# AH3761.net
KiCad netlist of a schematic drawn in EAGLE
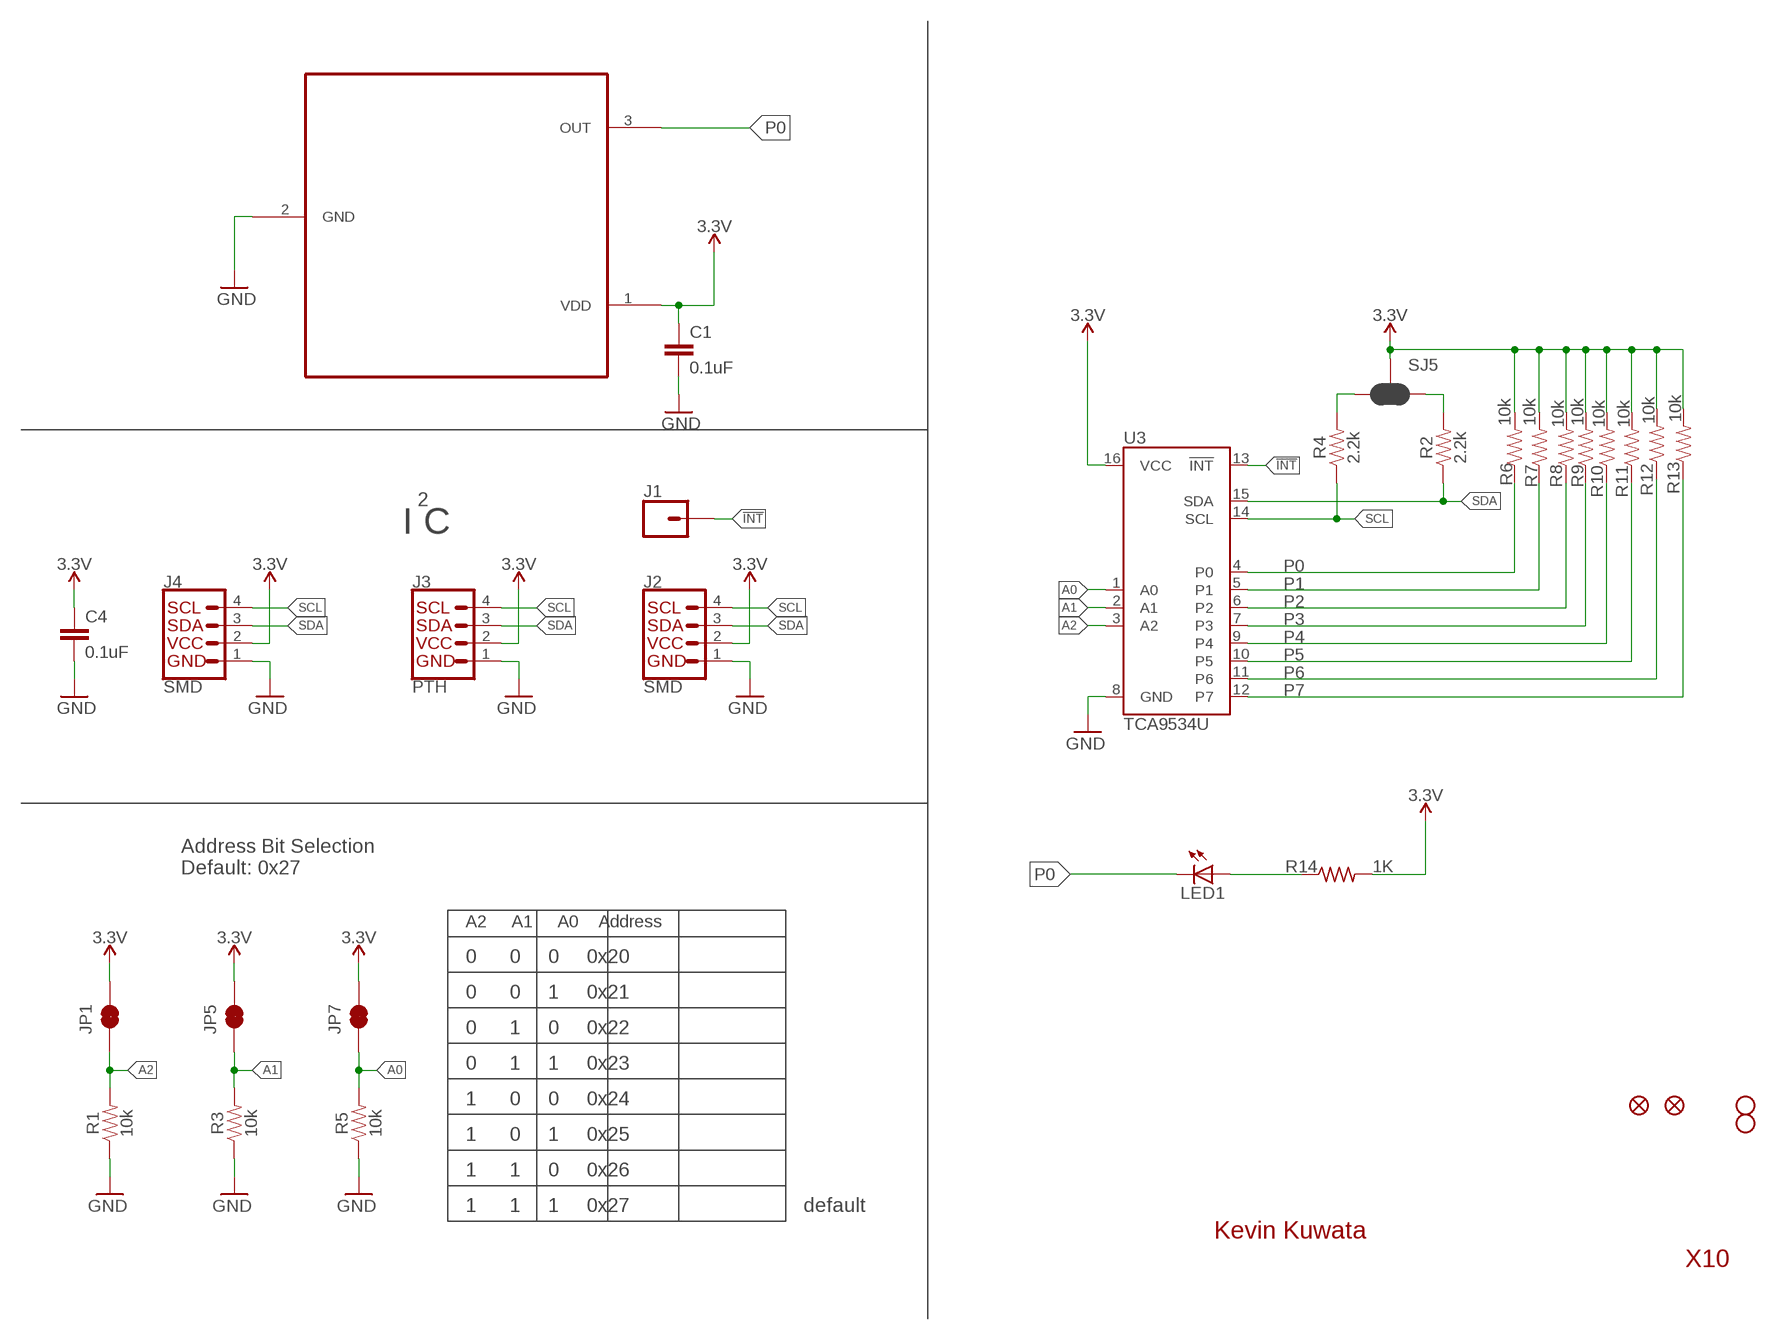
[diagram p0: schematic, sheet 1]

(export (version "E")
  (design (tool "Eeschema 10.0.6"))
  (components
    (comp (ref "C1")
      (value "0.1uF")
      (footprint "eagle-import:0603")
      (libsource (lib "eagle-import") (part "0.1UF-0603-25V-(+80/-20%)"))
    )
    (comp (ref "C4")
      (value "0.1uF")
      (footprint "eagle-import:0603")
      (libsource (lib "eagle-import") (part "0.1UF-0603-25V-(+80/-20%)"))
    )
    (comp (ref "J1")
      (value "CONN_01PTH_NO_SILK_YES_STOP")
      (footprint "eagle-import:1X01_NO_SILK")
      (libsource (lib "eagle-import") (part "CONN_01PTH_NO_SILK_YES_STOP"))
    )
    (comp (ref "J2")
      (value "SMD")
      (footprint "eagle-import:1X04_1MM_RA")
      (libsource (lib "eagle-import") (part "I2C_STANDARDJS-1MM"))
    )
    (comp (ref "J3")
      (value "PTH")
      (footprint "eagle-import:1X04_NO_SILK")
      (libsource (lib "eagle-import") (part "I2C_STANDARD_NO_SILK"))
    )
    (comp (ref "J4")
      (value "SMD")
      (footprint "eagle-import:1X04_1MM_RA")
      (libsource (lib "eagle-import") (part "I2C_STANDARDJS-1MM"))
    )
    (comp (ref "JP1")
      (value "JUMPER-SMT_2_NC_TRACE_NO-SILK")
      (footprint "eagle-import:SMT-JUMPER_2_NC_TRACE_NO-SILK")
      (libsource (lib "eagle-import") (part "JUMPER-SMT_2_NC_TRACE_NO-SILK"))
    )
    (comp (ref "JP2")
      (value "FIDUCIALUFIDUCIAL")
      (footprint "eagle-import:MICRO-FIDUCIAL")
      (libsource (lib "eagle-import") (part "FIDUCIALUFIDUCIAL"))
    )
    (comp (ref "JP3")
      (value "STAND-OFF")
      (footprint "eagle-import:STAND-OFF")
      (libsource (lib "eagle-import") (part "STAND-OFF"))
    )
    (comp (ref "JP4")
      (value "STAND-OFF")
      (footprint "eagle-import:STAND-OFF")
      (libsource (lib "eagle-import") (part "STAND-OFF"))
    )
    (comp (ref "JP5")
      (value "JUMPER-SMT_2_NC_TRACE_NO-SILK")
      (footprint "eagle-import:SMT-JUMPER_2_NC_TRACE_NO-SILK")
      (libsource (lib "eagle-import") (part "JUMPER-SMT_2_NC_TRACE_NO-SILK"))
    )
    (comp (ref "JP6")
      (value "FIDUCIALUFIDUCIAL")
      (footprint "eagle-import:MICRO-FIDUCIAL")
      (libsource (lib "eagle-import") (part "FIDUCIALUFIDUCIAL"))
    )
    (comp (ref "JP7")
      (value "JUMPER-SMT_2_NC_TRACE_NO-SILK")
      (footprint "eagle-import:SMT-JUMPER_2_NC_TRACE_NO-SILK")
      (libsource (lib "eagle-import") (part "JUMPER-SMT_2_NC_TRACE_NO-SILK"))
    )
    (comp (ref "LED1")
      (value "LEDCHIPLED_0603")
      (footprint "eagle-import:CHIPLED_0603")
      (libsource (lib "eagle-import") (part "LEDCHIPLED_0603"))
    )
    (comp (ref "R1")
      (value "10k")
      (footprint "eagle-import:0603")
      (libsource (lib "eagle-import") (part "2.2KOHM-0603-1/10W-1%"))
    )
    (comp (ref "R2")
      (value "2.2k")
      (footprint "eagle-import:0603")
      (libsource (lib "eagle-import") (part "2.2KOHM-0603-1/10W-1%"))
    )
    (comp (ref "R3")
      (value "10k")
      (footprint "eagle-import:0603")
      (libsource (lib "eagle-import") (part "2.2KOHM-0603-1/10W-1%"))
    )
    (comp (ref "R4")
      (value "2.2k")
      (footprint "eagle-import:0603")
      (libsource (lib "eagle-import") (part "2.2KOHM-0603-1/10W-1%"))
    )
    (comp (ref "R5")
      (value "10k")
      (footprint "eagle-import:0603")
      (libsource (lib "eagle-import") (part "2.2KOHM-0603-1/10W-1%"))
    )
    (comp (ref "R6")
      (value "10k")
      (footprint "eagle-import:0603")
      (libsource (lib "eagle-import") (part "10KOHM-0603-1/10W-1%"))
    )
    (comp (ref "R7")
      (value "10k")
      (footprint "eagle-import:0603")
      (libsource (lib "eagle-import") (part "10KOHM-0603-1/10W-1%"))
    )
    (comp (ref "R8")
      (value "10k")
      (footprint "eagle-import:0603")
      (libsource (lib "eagle-import") (part "10KOHM-0603-1/10W-1%"))
    )
    (comp (ref "R9")
      (value "10k")
      (footprint "eagle-import:0603")
      (libsource (lib "eagle-import") (part "10KOHM-0603-1/10W-1%"))
    )
    (comp (ref "R10")
      (value "10k")
      (footprint "eagle-import:0603")
      (libsource (lib "eagle-import") (part "10KOHM-0603-1/10W-1%"))
    )
    (comp (ref "R11")
      (value "10k")
      (footprint "eagle-import:0603")
      (libsource (lib "eagle-import") (part "10KOHM-0603-1/10W-1%"))
    )
    (comp (ref "R12")
      (value "10k")
      (footprint "eagle-import:0603")
      (libsource (lib "eagle-import") (part "10KOHM-0603-1/10W-1%"))
    )
    (comp (ref "R13")
      (value "10k")
      (footprint "eagle-import:0603")
      (libsource (lib "eagle-import") (part "10KOHM-0603-1/10W-1%"))
    )
    (comp (ref "R14")
      (value "1K")
      (footprint "eagle-import:R0603")
      (libsource (lib "eagle-import") (part "R-US_R0603"))
    )
    (comp (ref "SJ5")
      (value "SMT-JUMPER-_3-2-NC-PASTE_TALL")
      (footprint "eagle-import:SMT-JUMPER_3-2-NC-PASTE_SILK_TALLER_A")
      (libsource (lib "eagle-import") (part "SMT-JUMPER-_3-2-NC-PASTE_TALL"))
    )
    (comp (ref "U$1")
      (value "AH3761")
      (footprint "eagle-import:SC-59")
      (libsource (lib "eagle-import") (part "AH3761"))
    )
    (comp (ref "U3")
      (value "TCA9534U")
      (footprint "eagle-import:16SOIC")
      (libsource (lib "eagle-import") (part "TCA9534U"))
    )
  )
  (nets
    (net (code "1") (name "/P1") (class "Default")
      (node (ref "R7") (pin "1") (pinfunction "1_1") (pintype "passive"))
      (node (ref "U3") (pin "5") (pinfunction "P1_5") (pintype "bidirectional"))
    )
    (net (code "2") (name "/P2") (class "Default")
      (node (ref "R8") (pin "1") (pinfunction "1_1") (pintype "passive"))
      (node (ref "U3") (pin "6") (pinfunction "P2_6") (pintype "bidirectional"))
    )
    (net (code "3") (name "/P3") (class "Default")
      (node (ref "R9") (pin "1") (pinfunction "1_1") (pintype "passive"))
      (node (ref "U3") (pin "7") (pinfunction "P3_7") (pintype "bidirectional"))
    )
    (net (code "4") (name "/P4") (class "Default")
      (node (ref "R10") (pin "1") (pinfunction "1_1") (pintype "passive"))
      (node (ref "U3") (pin "9") (pinfunction "P4_9") (pintype "bidirectional"))
    )
    (net (code "5") (name "/P5") (class "Default")
      (node (ref "R11") (pin "1") (pinfunction "1_1") (pintype "passive"))
      (node (ref "U3") (pin "10") (pinfunction "P5_10") (pintype "bidirectional"))
    )
    (net (code "6") (name "/P6") (class "Default")
      (node (ref "R12") (pin "1") (pinfunction "1_1") (pintype "passive"))
      (node (ref "U3") (pin "11") (pinfunction "P6_11") (pintype "bidirectional"))
    )
    (net (code "7") (name "/P7") (class "Default")
      (node (ref "R13") (pin "1") (pinfunction "1_1") (pintype "passive"))
      (node (ref "U3") (pin "12") (pinfunction "P7_12") (pintype "bidirectional"))
    )
    (net (code "8") (name "/~{INT}") (class "Default")
      (node (ref "J1") (pin "1") (pinfunction "1_1") (pintype "passive"))
      (node (ref "U3") (pin "13") (pinfunction "~{INT}_13") (pintype "bidirectional"))
    )
    (net (code "9") (name "3.3V") (class "Default")
      (node (ref "C1") (pin "1") (pinfunction "1_1") (pintype "passive"))
      (node (ref "C4") (pin "1") (pinfunction "1_1") (pintype "passive"))
      (node (ref "J2") (pin "2") (pinfunction "VCC_2") (pintype "power_in"))
      (node (ref "J3") (pin "2") (pinfunction "VCC_2") (pintype "power_in"))
      (node (ref "J4") (pin "2") (pinfunction "VCC_2") (pintype "power_in"))
      (node (ref "JP1") (pin "2") (pinfunction "2_2") (pintype "passive"))
      (node (ref "JP5") (pin "2") (pinfunction "2_2") (pintype "passive"))
      (node (ref "JP7") (pin "2") (pinfunction "2_2") (pintype "passive"))
      (node (ref "R10") (pin "2") (pinfunction "2_2") (pintype "passive"))
      (node (ref "R11") (pin "2") (pinfunction "2_2") (pintype "passive"))
      (node (ref "R12") (pin "2") (pinfunction "2_2") (pintype "passive"))
      (node (ref "R13") (pin "2") (pinfunction "2_2") (pintype "passive"))
      (node (ref "R14") (pin "2") (pinfunction "2_2") (pintype "passive"))
      (node (ref "R6") (pin "2") (pinfunction "2_2") (pintype "passive"))
      (node (ref "R7") (pin "2") (pinfunction "2_2") (pintype "passive"))
      (node (ref "R8") (pin "2") (pinfunction "2_2") (pintype "passive"))
      (node (ref "R9") (pin "2") (pinfunction "2_2") (pintype "passive"))
      (node (ref "SJ5") (pin "2") (pinfunction "2_2") (pintype "passive"))
      (node (ref "U$1") (pin "1") (pinfunction "VDD_1") (pintype "power_in"))
      (node (ref "U3") (pin "16") (pinfunction "VCC_16") (pintype "bidirectional"))
    )
    (net (code "10") (name "A0") (class "Default")
      (node (ref "JP7") (pin "1") (pinfunction "1_1") (pintype "passive"))
      (node (ref "R5") (pin "2") (pinfunction "2_2") (pintype "passive"))
      (node (ref "U3") (pin "1") (pinfunction "A0_1") (pintype "bidirectional"))
    )
    (net (code "11") (name "A1") (class "Default")
      (node (ref "JP5") (pin "1") (pinfunction "1_1") (pintype "passive"))
      (node (ref "R3") (pin "2") (pinfunction "2_2") (pintype "passive"))
      (node (ref "U3") (pin "2") (pinfunction "A1_2") (pintype "bidirectional"))
    )
    (net (code "12") (name "A2") (class "Default")
      (node (ref "JP1") (pin "1") (pinfunction "1_1") (pintype "passive"))
      (node (ref "R1") (pin "2") (pinfunction "2_2") (pintype "passive"))
      (node (ref "U3") (pin "3") (pinfunction "A2_3") (pintype "bidirectional"))
    )
    (net (code "13") (name "GND") (class "Default")
      (node (ref "C1") (pin "2") (pinfunction "2_2") (pintype "passive"))
      (node (ref "C4") (pin "2") (pinfunction "2_2") (pintype "passive"))
      (node (ref "J2") (pin "1") (pinfunction "GND_1") (pintype "power_in"))
      (node (ref "J3") (pin "1") (pinfunction "GND_1") (pintype "power_in"))
      (node (ref "J4") (pin "1") (pinfunction "GND_1") (pintype "power_in"))
      (node (ref "R1") (pin "1") (pinfunction "1_1") (pintype "passive"))
      (node (ref "R3") (pin "1") (pinfunction "1_1") (pintype "passive"))
      (node (ref "R5") (pin "1") (pinfunction "1_1") (pintype "passive"))
      (node (ref "U$1") (pin "2") (pinfunction "GND_2") (pintype "bidirectional"))
      (node (ref "U3") (pin "8") (pinfunction "GND_8") (pintype "bidirectional"))
    )
    (net (code "14") (name "Net-(LED1-PadA)") (class "Default")
      (node (ref "LED1") (pin "A") (pinfunction "A_A") (pintype "passive"))
      (node (ref "R14") (pin "1") (pinfunction "1_1") (pintype "passive"))
    )
    (net (code "15") (name "Net-(R2-Pad2)") (class "Default")
      (node (ref "R2") (pin "2") (pinfunction "2_2") (pintype "passive"))
      (node (ref "SJ5") (pin "1") (pinfunction "1_1") (pintype "passive"))
    )
    (net (code "16") (name "Net-(R4-Pad2)") (class "Default")
      (node (ref "R4") (pin "2") (pinfunction "2_2") (pintype "passive"))
      (node (ref "SJ5") (pin "3") (pinfunction "3_3") (pintype "passive"))
    )
    (net (code "17") (name "P0") (class "Default")
      (node (ref "LED1") (pin "C") (pinfunction "C_C") (pintype "passive"))
      (node (ref "R6") (pin "1") (pinfunction "1_1") (pintype "passive"))
      (node (ref "U$1") (pin "3") (pinfunction "OUT_3") (pintype "bidirectional"))
      (node (ref "U3") (pin "4") (pinfunction "P0_4") (pintype "bidirectional"))
    )
    (net (code "18") (name "SCL") (class "Default")
      (node (ref "J2") (pin "4") (pinfunction "SCL_4") (pintype "passive"))
      (node (ref "J3") (pin "4") (pinfunction "SCL_4") (pintype "passive"))
      (node (ref "J4") (pin "4") (pinfunction "SCL_4") (pintype "passive"))
      (node (ref "R4") (pin "1") (pinfunction "1_1") (pintype "passive"))
      (node (ref "U3") (pin "14") (pinfunction "SCL_14") (pintype "bidirectional"))
    )
    (net (code "19") (name "SDA") (class "Default")
      (node (ref "J2") (pin "3") (pinfunction "SDA_3") (pintype "passive"))
      (node (ref "J3") (pin "3") (pinfunction "SDA_3") (pintype "passive"))
      (node (ref "J4") (pin "3") (pinfunction "SDA_3") (pintype "passive"))
      (node (ref "R2") (pin "1") (pinfunction "1_1") (pintype "passive"))
      (node (ref "U3") (pin "15") (pinfunction "SDA_15") (pintype "bidirectional"))
    )
  )
)
